# Part10_SD_card.net
KiCad netlist of a schematic drawn in Altium Designer
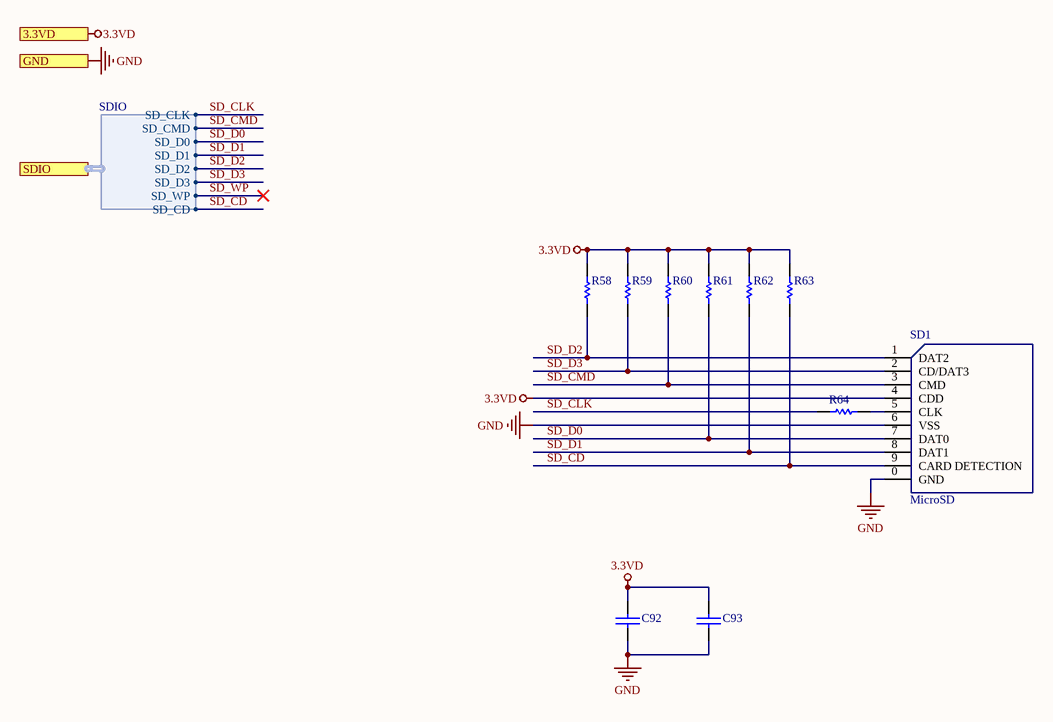
[diagram p0: Part10_SD_card.SchDoc]

(export (version "E")
  (design (tool "Eeschema 10.0.6"))
  (components
    (comp (ref "C92")
      (value "10uF")
      (footprint "0402C")
      (description "无极性电容")
      (libsource (lib "电容") (part "CAP"))
    )
    (comp (ref "C93")
      (value "100nF")
      (footprint "0402C")
      (description "无极性电容")
      (libsource (lib "电容") (part "CAP"))
    )
    (comp (ref "R58") (value "10K") (footprint "0402R") (libsource (lib "电阻") (part "RES")))
    (comp (ref "R59") (value "10K") (footprint "0402R") (libsource (lib "电阻") (part "RES")))
    (comp (ref "R60") (value "10K") (footprint "0402R") (libsource (lib "电阻") (part "RES")))
    (comp (ref "R61") (value "10K") (footprint "0402R") (libsource (lib "电阻") (part "RES")))
    (comp (ref "R62") (value "10K") (footprint "0402R") (libsource (lib "电阻") (part "RES")))
    (comp (ref "R63") (value "10K") (footprint "0402R") (libsource (lib "电阻") (part "RES")))
    (comp (ref "R64") (value "22R") (footprint "0402R") (libsource (lib "电阻") (part "RES")))
    (comp (ref "SD1") (value "MicroSD") (footprint "Micro SD") (libsource (lib "SD Card") (part "MicroSD")))
  )
  (nets
    (net (code "2") (name "/SD_CD") (class "Default")
      (node (ref "R63") (pin "2") (pinfunction "2_2") (pintype "passive"))
      (node (ref "SD1") (pin "9") (pinfunction "CARD_DETECTION_9") (pintype "passive"))
    )
    (net (code "3") (name "/SD_CLK") (class "Default")
      (node (ref "R64") (pin "1") (pinfunction "1_1") (pintype "passive"))
    )
    (net (code "4") (name "/SD_CMD") (class "Default")
      (node (ref "R60") (pin "2") (pinfunction "2_2") (pintype "passive"))
      (node (ref "SD1") (pin "3") (pinfunction "CMD_3") (pintype "passive"))
    )
    (net (code "5") (name "/SD_D0") (class "Default")
      (node (ref "R61") (pin "2") (pinfunction "2_2") (pintype "passive"))
      (node (ref "SD1") (pin "7") (pinfunction "DAT0_7") (pintype "passive"))
    )
    (net (code "6") (name "/SD_D1") (class "Default")
      (node (ref "R62") (pin "2") (pinfunction "2_2") (pintype "passive"))
      (node (ref "SD1") (pin "8") (pinfunction "DAT1_8") (pintype "passive"))
    )
    (net (code "7") (name "/SD_D2") (class "Default")
      (node (ref "R58") (pin "2") (pinfunction "2_2") (pintype "passive"))
      (node (ref "SD1") (pin "1") (pinfunction "DAT2_1") (pintype "passive"))
    )
    (net (code "8") (name "/SD_D3") (class "Default")
      (node (ref "R59") (pin "2") (pinfunction "2_2") (pintype "passive"))
      (node (ref "SD1") (pin "2") (pinfunction "CD/DAT3_2") (pintype "passive"))
    )
    (net (code "11") (name "3.3VD") (class "Default")
      (node (ref "C92") (pin "1") (pinfunction "1_1") (pintype "passive"))
      (node (ref "C93") (pin "1") (pinfunction "1_1") (pintype "passive"))
      (node (ref "R58") (pin "1") (pinfunction "1_1") (pintype "passive"))
      (node (ref "R59") (pin "1") (pinfunction "1_1") (pintype "passive"))
      (node (ref "R60") (pin "1") (pinfunction "1_1") (pintype "passive"))
      (node (ref "R61") (pin "1") (pinfunction "1_1") (pintype "passive"))
      (node (ref "R62") (pin "1") (pinfunction "1_1") (pintype "passive"))
      (node (ref "R63") (pin "1") (pinfunction "1_1") (pintype "passive"))
      (node (ref "SD1") (pin "4") (pinfunction "CDD_4") (pintype "passive"))
    )
    (net (code "12") (name "GND") (class "Default")
      (node (ref "C92") (pin "2") (pinfunction "2_2") (pintype "passive"))
      (node (ref "C93") (pin "2") (pinfunction "2_2") (pintype "passive"))
      (node (ref "SD1") (pin "0") (pinfunction "GND_0") (pintype "passive"))
      (node (ref "SD1") (pin "6") (pinfunction "VSS_6") (pintype "passive"))
    )
    (net (code "13") (name "Net-(SD1-CLK)") (class "Default")
      (node (ref "R64") (pin "2") (pinfunction "2_2") (pintype "passive"))
      (node (ref "SD1") (pin "5") (pinfunction "CLK_5") (pintype "passive"))
    )
  )
)
